# Holiday_r2.net
KiCad netlist of a schematic drawn in Altium Designer
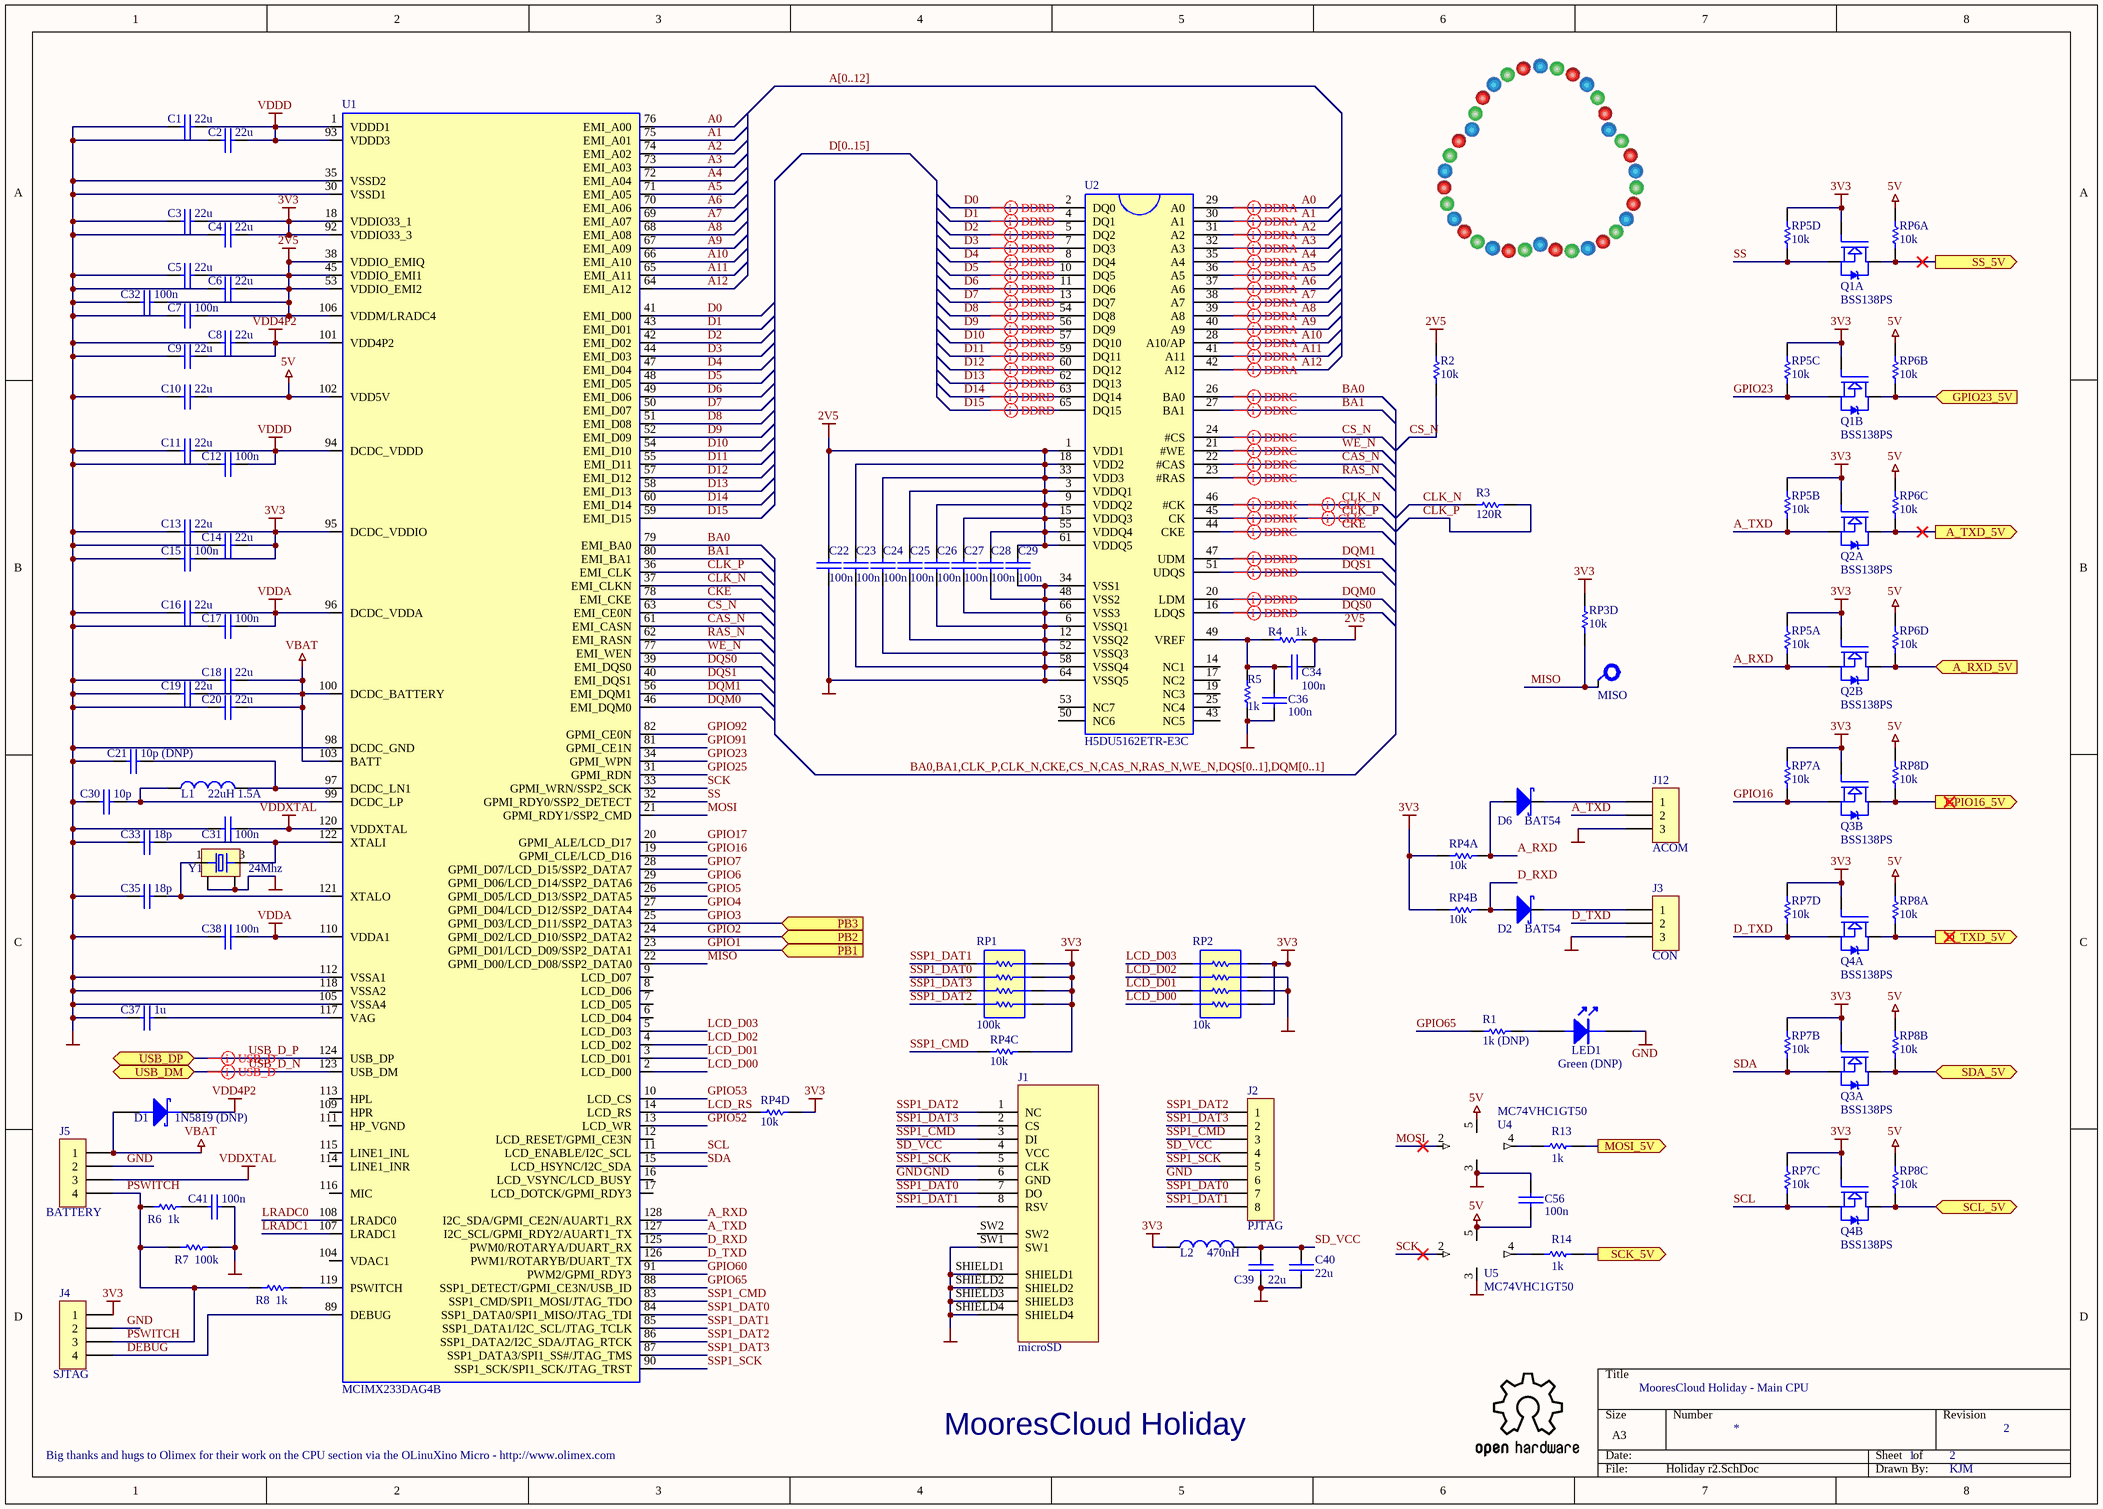
[diagram p0: Holiday r2.SchDoc]

(export (version "E")
  (design (tool "Eeschema 10.0.6"))
  (components
    (comp (ref "C1")
      (value "22u")
      (footprint "ARA_0603")
      (description "Capacitor")
      (libsource (lib "Kean2013") (part "CAP"))
    )
    (comp (ref "C2")
      (value "22u")
      (footprint "ARA_0603")
      (description "Capacitor")
      (libsource (lib "Kean2013") (part "CAP"))
    )
    (comp (ref "C3")
      (value "22u")
      (footprint "ARA_0603")
      (description "Capacitor")
      (libsource (lib "Kean2013") (part "CAP"))
    )
    (comp (ref "C4")
      (value "22u")
      (footprint "ARA_0603")
      (description "Capacitor")
      (libsource (lib "Kean2013") (part "CAP"))
    )
    (comp (ref "C5")
      (value "22u")
      (footprint "ARA_0603")
      (description "Capacitor")
      (libsource (lib "Kean2013") (part "CAP"))
    )
    (comp (ref "C6")
      (value "22u")
      (footprint "ARA_0603")
      (description "Capacitor")
      (libsource (lib "Kean2013") (part "CAP"))
    )
    (comp (ref "C7")
      (value "100n")
      (footprint "ARA_0603")
      (description "Capacitor")
      (libsource (lib "Kean2013") (part "CAP"))
    )
    (comp (ref "C8")
      (value "22u")
      (footprint "ARA_0603")
      (description "Capacitor")
      (libsource (lib "Kean2013") (part "CAP"))
    )
    (comp (ref "C9")
      (value "22u")
      (footprint "ARA_0603")
      (description "Capacitor")
      (libsource (lib "Kean2013") (part "CAP"))
    )
    (comp (ref "C10")
      (value "22u")
      (footprint "ARA_0603")
      (description "Capacitor")
      (libsource (lib "Kean2013") (part "CAP"))
    )
    (comp (ref "C11")
      (value "22u")
      (footprint "ARA_0603")
      (description "Capacitor")
      (libsource (lib "Kean2013") (part "CAP"))
    )
    (comp (ref "C12")
      (value "100n")
      (footprint "ARA_0603")
      (description "Capacitor")
      (libsource (lib "Kean2013") (part "CAP"))
    )
    (comp (ref "C13")
      (value "22u")
      (footprint "ARA_0603")
      (description "Capacitor")
      (libsource (lib "Kean2013") (part "CAP"))
    )
    (comp (ref "C14")
      (value "22u")
      (footprint "ARA_0603")
      (description "Capacitor")
      (libsource (lib "Kean2013") (part "CAP"))
    )
    (comp (ref "C15")
      (value "100n")
      (footprint "ARA_0603")
      (description "Capacitor")
      (libsource (lib "Kean2013") (part "CAP"))
    )
    (comp (ref "C16")
      (value "22u")
      (footprint "ARA_0603")
      (description "Capacitor")
      (libsource (lib "Kean2013") (part "CAP"))
    )
    (comp (ref "C17")
      (value "100n")
      (footprint "ARA_0603")
      (description "Capacitor")
      (libsource (lib "Kean2013") (part "CAP"))
    )
    (comp (ref "C18")
      (value "22u")
      (footprint "ARA_0603")
      (description "Capacitor")
      (libsource (lib "Kean2013") (part "CAP"))
    )
    (comp (ref "C19")
      (value "22u")
      (footprint "ARA_0603")
      (description "Capacitor")
      (libsource (lib "Kean2013") (part "CAP"))
    )
    (comp (ref "C20")
      (value "22u")
      (footprint "ARA_0603")
      (description "Capacitor")
      (libsource (lib "Kean2013") (part "CAP"))
    )
    (comp (ref "C21")
      (value "10p (DNP)")
      (footprint "ARA_0603")
      (description "Capacitor")
      (libsource (lib "Kean2013") (part "CAP"))
    )
    (comp (ref "C22")
      (value "100n")
      (footprint "ARA_0603")
      (description "Capacitor")
      (libsource (lib "Kean2013") (part "CAP"))
    )
    (comp (ref "C23")
      (value "100n")
      (footprint "ARA_0603")
      (description "Capacitor")
      (libsource (lib "Kean2013") (part "CAP"))
    )
    (comp (ref "C24")
      (value "100n")
      (footprint "ARA_0603")
      (description "Capacitor")
      (libsource (lib "Kean2013") (part "CAP"))
    )
    (comp (ref "C25")
      (value "100n")
      (footprint "ARA_0603")
      (description "Capacitor")
      (libsource (lib "Kean2013") (part "CAP"))
    )
    (comp (ref "C26")
      (value "100n")
      (footprint "ARA_0603")
      (description "Capacitor")
      (libsource (lib "Kean2013") (part "CAP"))
    )
    (comp (ref "C27")
      (value "100n")
      (footprint "ARA_0603")
      (description "Capacitor")
      (libsource (lib "Kean2013") (part "CAP"))
    )
    (comp (ref "C28")
      (value "100n")
      (footprint "ARA_0603")
      (description "Capacitor")
      (libsource (lib "Kean2013") (part "CAP"))
    )
    (comp (ref "C29")
      (value "100n")
      (footprint "ARA_0603")
      (description "Capacitor")
      (libsource (lib "Kean2013") (part "CAP"))
    )
    (comp (ref "C30")
      (value "10p")
      (footprint "ARA_0603")
      (description "Capacitor")
      (libsource (lib "Kean2013") (part "CAP"))
    )
    (comp (ref "C31")
      (value "100n")
      (footprint "ARA_0603")
      (description "Capacitor")
      (libsource (lib "Kean2013") (part "CAP"))
    )
    (comp (ref "C32")
      (value "100n")
      (footprint "ARA_0603")
      (description "Capacitor")
      (libsource (lib "Kean2013") (part "CAP"))
    )
    (comp (ref "C33")
      (value "18p")
      (footprint "ARA_0603")
      (description "Capacitor")
      (libsource (lib "Kean2013") (part "CAP"))
    )
    (comp (ref "C34")
      (value "100n")
      (footprint "ARA_0603")
      (description "Capacitor")
      (libsource (lib "Kean2013") (part "CAP"))
    )
    (comp (ref "C35")
      (value "18p")
      (footprint "ARA_0603")
      (description "Capacitor")
      (libsource (lib "Kean2013") (part "CAP"))
    )
    (comp (ref "C36")
      (value "100n")
      (footprint "ARA_0603")
      (description "Capacitor")
      (libsource (lib "Kean2013") (part "CAP"))
    )
    (comp (ref "C37")
      (value "1u")
      (footprint "ARA_0603")
      (description "Capacitor")
      (libsource (lib "Kean2013") (part "CAP"))
    )
    (comp (ref "C38")
      (value "100n")
      (footprint "ARA_0603")
      (description "Capacitor")
      (libsource (lib "Kean2013") (part "CAP"))
    )
    (comp (ref "C39")
      (value "22u")
      (footprint "ARA_0603")
      (description "Capacitor")
      (libsource (lib "Kean2013") (part "CAP"))
    )
    (comp (ref "C40")
      (value "22u")
      (footprint "ARA_0603")
      (description "Capacitor")
      (libsource (lib "Kean2013") (part "CAP"))
    )
    (comp (ref "C41")
      (value "100n")
      (footprint "ARA_0603")
      (description "Capacitor")
      (libsource (lib "Kean2013") (part "CAP"))
    )
    (comp (ref "C56")
      (value "100n")
      (footprint "ARA_0603")
      (description "Capacitor")
      (libsource (lib "Kean2013") (part "CAP"))
    )
    (comp (ref "D1")
      (value "1N5819 (DNP)")
      (footprint "SOD-123")
      (description "Schottky Diode 1N5819HW (DNP)")
      (libsource (lib "Kean2013") (part "DIODE SCHOTTKY"))
    )
    (comp (ref "D2")
      (value "BAT54")
      (footprint "ARA_SOT-23")
      (description "Schottky Diode")
      (libsource (lib "Kean2013") (part "BAT54"))
    )
    (comp (ref "D6")
      (value "BAT54")
      (footprint "ARA_SOT-23")
      (description "Schottky Diode")
      (libsource (lib "Kean2013") (part "BAT54"))
    )
    (comp (ref "J1")
      (value "microSD")
      (footprint "MICROSD-47309-3751 WITH CARD")
      (description "microSD Socket Push/Pull")
      (libsource (lib "Kean2013") (part "microSD"))
    )
    (comp (ref "J2")
      (value "PJTAG")
      (footprint "53047-08")
      (description "Connector")
      (libsource (lib "Kean2013") (part "CON8"))
    )
    (comp (ref "J3")
      (value "CON")
      (footprint "HDR1X3")
      (description "Connector")
      (libsource (lib "Kean2013") (part "CON3"))
    )
    (comp (ref "J4")
      (value "SJTAG")
      (footprint "HDR1X4")
      (description "Connector")
      (libsource (lib "Kean2013") (part "CON4"))
    )
    (comp (ref "J5")
      (value "BATTERY")
      (footprint "HDR1X4")
      (description "Connector")
      (libsource (lib "Kean2013") (part "CON4"))
    )
    (comp (ref "J12")
      (value "ACOM")
      (footprint "HDR1X3")
      (description "Connector")
      (libsource (lib "Kean2013") (part "CON3"))
    )
    (comp (ref "L1")
      (value "22uH 1.5A")
      (footprint "RCL_L7078")
      (description "Inductor")
      (libsource (lib "Kean2013") (part "Inductor"))
    )
    (comp (ref "L2")
      (value "470nH")
      (footprint "ARA_0805")
      (description "Ferrite")
      (libsource (lib "Kean2013") (part "Inductor"))
    )
    (comp (ref "LED1")
      (value "Green (DNP)")
      (footprint "LED_0805")
      (description "LED")
      (libsource (lib "Kean2013") (part "LED"))
    )
    (comp (ref "Q1")
      (value "BSS138PS")
      (footprint "ARA_SOT-363")
      (description "Dual N Channel MOSFET")
      (libsource (lib "Kean2013") (part "BSS138PS"))
    )
    (comp (ref "Q2")
      (value "BSS138PS")
      (footprint "ARA_SOT-363")
      (description "Dual N Channel MOSFET")
      (libsource (lib "Kean2013") (part "BSS138PS"))
    )
    (comp (ref "Q3")
      (value "BSS138PS")
      (footprint "ARA_SOT-363")
      (description "Dual N Channel MOSFET")
      (libsource (lib "Kean2013") (part "BSS138PS"))
    )
    (comp (ref "Q4")
      (value "BSS138PS")
      (footprint "ARA_SOT-363")
      (description "Dual N Channel MOSFET")
      (libsource (lib "Kean2013") (part "BSS138PS"))
    )
    (comp (ref "R1")
      (value "1k (DNP)")
      (footprint "ARA_0603")
      (description "Resistor")
      (libsource (lib "Kean2013") (part "Res Semi"))
    )
    (comp (ref "R2")
      (value "10k")
      (footprint "ARA_0603")
      (description "Resistor")
      (libsource (lib "Kean2013") (part "Res Semi"))
    )
    (comp (ref "R3")
      (value "120R")
      (footprint "ARA_0603")
      (description "Resistor")
      (libsource (lib "Kean2013") (part "Res Semi"))
    )
    (comp (ref "R4")
      (value "1k")
      (footprint "ARA_0603")
      (description "Resistor")
      (libsource (lib "Kean2013") (part "Res Semi"))
    )
    (comp (ref "R5")
      (value "1k")
      (footprint "ARA_0603")
      (description "Resistor")
      (libsource (lib "Kean2013") (part "Res Semi"))
    )
    (comp (ref "R6")
      (value "1k")
      (footprint "ARA_0603")
      (description "Resistor")
      (libsource (lib "Kean2013") (part "Res Semi"))
    )
    (comp (ref "R7")
      (value "100k")
      (footprint "ARA_0603")
      (description "Resistor")
      (libsource (lib "Kean2013") (part "Res Semi"))
    )
    (comp (ref "R8")
      (value "1k")
      (footprint "ARA_0603")
      (description "Resistor")
      (libsource (lib "Kean2013") (part "Res Semi"))
    )
    (comp (ref "R13")
      (value "1k")
      (footprint "ARA_0603")
      (description "Resistor")
      (libsource (lib "Kean2013") (part "Res Semi"))
    )
    (comp (ref "R14")
      (value "1k")
      (footprint "ARA_0603")
      (description "Resistor")
      (libsource (lib "Kean2013") (part "Res Semi"))
    )
    (comp (ref "RP1")
      (value "100k")
      (footprint "RESPACK_0603x4")
      (description "Resistor Pack 4x0603")
      (libsource (lib "Kean2013") (part "RESISTOR_PACK_4_1206"))
    )
    (comp (ref "RP2")
      (value "10k")
      (footprint "RESPACK_0603x4")
      (description "Resistor Pack 4x0603")
      (libsource (lib "Kean2013") (part "RESISTOR_PACK_4_1206"))
    )
    (comp (ref "RP3")
      (value "10k")
      (footprint "RESPACK_0603x4")
      (description "Resistor Pack 4x0603")
      (libsource (lib "Kean2013") (part "RESISTOR_PACK_4_1206_SPLIT"))
    )
    (comp (ref "RP4")
      (value "10k")
      (footprint "RESPACK_0603x4")
      (description "Resistor Pack 4x0603")
      (libsource (lib "Kean2013") (part "RESISTOR_PACK_4_1206_SPLIT"))
    )
    (comp (ref "RP5")
      (value "10k")
      (footprint "RESPACK_0603x4")
      (description "Resistor Pack 4x0603")
      (libsource (lib "Kean2013") (part "RESISTOR_PACK_4_1206_SPLIT"))
    )
    (comp (ref "RP6")
      (value "10k")
      (footprint "RESPACK_0603x4")
      (description "Resistor Pack 4x0603")
      (libsource (lib "Kean2013") (part "RESISTOR_PACK_4_1206_SPLIT"))
    )
    (comp (ref "RP7")
      (value "10k")
      (footprint "RESPACK_0603x4")
      (description "Resistor Pack 4x0603")
      (libsource (lib "Kean2013") (part "RESISTOR_PACK_4_1206_SPLIT"))
    )
    (comp (ref "RP8")
      (value "10k")
      (footprint "RESPACK_0603x4")
      (description "Resistor Pack 4x0603")
      (libsource (lib "Kean2013") (part "RESISTOR_PACK_4_1206_SPLIT"))
    )
    (comp (ref "TP1")
      (value "MISO")
      (footprint "SMD_TESTTERMINAL")
      (description "Test Point")
      (libsource (lib "Kean2013") (part "TESTTERMINAL"))
    )
    (comp (ref "U1")
      (value "MCIMX233DAG4B")
      (footprint "LQFP128")
      (description "Freescale i.MX233 128 pin LQFP package")
      (libsource (lib "Kean2013") (part "MCIMX233DAG4B"))
    )
    (comp (ref "U2")
      (value "H5DU5162ETR-E3C")
      (footprint "TSOP-II-66")
      (description "SDRAM DDR400 66TSOP-II")
      (libsource (lib "Kean2013") (part "H5DU5162ETR-E3C"))
    )
    (comp (ref "U4")
      (value "MC74VHC1GT50")
      (footprint "ARA_SOT-23-5L")
      (description "CMOS Logic Level Shifter")
      (libsource (lib "Kean2013") (part "MC74VHC1GT50"))
    )
    (comp (ref "U5")
      (value "MC74VHC1GT50")
      (footprint "ARA_SOT-23-5L")
      (description "CMOS Logic Level Shifter")
      (libsource (lib "Kean2013") (part "MC74VHC1GT50"))
    )
    (comp (ref "Y1")
      (value "24Mhz")
      (footprint "CRYSTAL_ABMM2")
      (description "ABMM2 SMD Crystal")
      (libsource (lib "Kean2013") (part "CRYSTAL_ABMM2"))
    )
  )
  (nets
    (net (code "2") (name "/A0") (class "Default")
      (node (ref "U1") (pin "76") (pinfunction "EMI_A00_76") (pintype "passive"))
      (node (ref "U2") (pin "29") (pinfunction "A0_29") (pintype "passive"))
    )
    (net (code "3") (name "/A1") (class "Default")
      (node (ref "U1") (pin "75") (pinfunction "EMI_A01_75") (pintype "passive"))
      (node (ref "U2") (pin "30") (pinfunction "A1_30") (pintype "passive"))
    )
    (net (code "4") (name "/A2") (class "Default")
      (node (ref "U1") (pin "74") (pinfunction "EMI_A02_74") (pintype "passive"))
      (node (ref "U2") (pin "31") (pinfunction "A2_31") (pintype "passive"))
    )
    (net (code "5") (name "/A3") (class "Default")
      (node (ref "U1") (pin "73") (pinfunction "EMI_A03_73") (pintype "passive"))
      (node (ref "U2") (pin "32") (pinfunction "A3_32") (pintype "passive"))
    )
    (net (code "6") (name "/A4") (class "Default")
      (node (ref "U1") (pin "72") (pinfunction "EMI_A04_72") (pintype "passive"))
      (node (ref "U2") (pin "35") (pinfunction "A4_35") (pintype "passive"))
    )
    (net (code "7") (name "/A5") (class "Default")
      (node (ref "U1") (pin "71") (pinfunction "EMI_A05_71") (pintype "passive"))
      (node (ref "U2") (pin "36") (pinfunction "A5_36") (pintype "passive"))
    )
    (net (code "8") (name "/A6") (class "Default")
      (node (ref "U1") (pin "70") (pinfunction "EMI_A06_70") (pintype "passive"))
      (node (ref "U2") (pin "37") (pinfunction "A6_37") (pintype "passive"))
    )
    (net (code "9") (name "/A7") (class "Default")
      (node (ref "U1") (pin "69") (pinfunction "EMI_A07_69") (pintype "passive"))
      (node (ref "U2") (pin "38") (pinfunction "A7_38") (pintype "passive"))
    )
    (net (code "10") (name "/A8") (class "Default")
      (node (ref "U1") (pin "68") (pinfunction "EMI_A08_68") (pintype "passive"))
      (node (ref "U2") (pin "39") (pinfunction "A8_39") (pintype "passive"))
    )
    (net (code "11") (name "/A9") (class "Default")
      (node (ref "U1") (pin "67") (pinfunction "EMI_A09_67") (pintype "passive"))
      (node (ref "U2") (pin "40") (pinfunction "A9_40") (pintype "passive"))
    )
    (net (code "12") (name "/A10") (class "Default")
      (node (ref "U1") (pin "66") (pinfunction "EMI_A10_66") (pintype "passive"))
      (node (ref "U2") (pin "28") (pinfunction "A10/AP_28") (pintype "passive"))
    )
    (net (code "13") (name "/A11") (class "Default")
      (node (ref "U1") (pin "65") (pinfunction "EMI_A11_65") (pintype "passive"))
      (node (ref "U2") (pin "41") (pinfunction "A11_41") (pintype "passive"))
    )
    (net (code "14") (name "/A12") (class "Default")
      (node (ref "U1") (pin "64") (pinfunction "EMI_A12_64") (pintype "passive"))
      (node (ref "U2") (pin "42") (pinfunction "A12_42") (pintype "passive"))
    )
    (net (code "16") (name "/A_RXD") (class "Default")
      (node (ref "D6") (pin "1") (pinfunction "A_1") (pintype "passive"))
      (node (ref "Q2") (pin "4") (pinfunction "S2_4") (pintype "passive"))
      (node (ref "RP4") (pin "1.1") (pinfunction "1.1_1.1") (pintype "passive"))
      (node (ref "RP5") (pin "1.1") (pinfunction "1.1_1.1") (pintype "passive"))
      (node (ref "U1") (pin "128") (pinfunction "I2C_SDA/GPMI_CE2N/AUART1_RX_128") (pintype "passive"))
    )
    (net (code "17") (name "/A_RXD_5V") (class "Default")
      (node (ref "Q2") (pin "3") (pinfunction "D2_3") (pintype "passive"))
      (node (ref "RP6") (pin "4.1") (pinfunction "4.1_4.1") (pintype "passive"))
    )
    (net (code "18") (name "/A_TXD") (class "Default")
      (node (ref "J12") (pin "2") (pinfunction "2_2") (pintype "passive"))
      (node (ref "Q2") (pin "1") (pinfunction "S1_1") (pintype "passive"))
      (node (ref "RP5") (pin "2.1") (pinfunction "2.1_2.1") (pintype "passive"))
      (node (ref "U1") (pin "127") (pinfunction "I2C_SCL/GPMI_RDY2/AUART1_TX_127") (pintype "passive"))
    )
    (net (code "19") (name "/A_TXD_5V") (class "Default")
      (node (ref "Q2") (pin "6") (pinfunction "D1_6") (pintype "passive"))
      (node (ref "RP6") (pin "3.1") (pinfunction "3.1_3.1") (pintype "passive"))
    )
    (net (code "20") (name "/BA0") (class "Default")
      (node (ref "U1") (pin "79") (pinfunction "EMI_BA0_79") (pintype "passive"))
      (node (ref "U2") (pin "26") (pinfunction "BA0_26") (pintype "passive"))
    )
    (net (code "21") (name "/BA1") (class "Default")
      (node (ref "U1") (pin "80") (pinfunction "EMI_BA1_80") (pintype "passive"))
      (node (ref "U2") (pin "27") (pinfunction "BA1_27") (pintype "passive"))
    )
    (net (code "22") (name "/CAS_N") (class "Default")
      (node (ref "U1") (pin "61") (pinfunction "EMI_CASN_61") (pintype "passive"))
      (node (ref "U2") (pin "22") (pinfunction "#CAS_22") (pintype "passive"))
    )
    (net (code "23") (name "/CKE") (class "Default")
      (node (ref "U1") (pin "78") (pinfunction "EMI_CKE_78") (pintype "passive"))
      (node (ref "U2") (pin "44") (pinfunction "CKE_44") (pintype "passive"))
    )
    (net (code "24") (name "/CLK_N") (class "Default")
      (node (ref "R3") (pin "1") (pinfunction "1_1") (pintype "passive"))
      (node (ref "U1") (pin "37") (pinfunction "EMI_CLKN_37") (pintype "passive"))
      (node (ref "U2") (pin "46") (pinfunction "#CK_46") (pintype "passive"))
    )
    (net (code "25") (name "/CLK_P") (class "Default")
      (node (ref "R3") (pin "2") (pinfunction "2_2") (pintype "passive"))
      (node (ref "U1") (pin "36") (pinfunction "EMI_CLK_36") (pintype "passive"))
      (node (ref "U2") (pin "45") (pinfunction "CK_45") (pintype "passive"))
    )
    (net (code "26") (name "/CS_N") (class "Default")
      (node (ref "R2") (pin "1") (pinfunction "1_1") (pintype "passive"))
      (node (ref "U1") (pin "63") (pinfunction "EMI_CE0N_63") (pintype "passive"))
      (node (ref "U2") (pin "24") (pinfunction "#CS_24") (pintype "passive"))
    )
    (net (code "27") (name "/D0") (class "Default")
      (node (ref "U1") (pin "41") (pinfunction "EMI_D00_41") (pintype "passive"))
      (node (ref "U2") (pin "2") (pinfunction "DQ0_2") (pintype "passive"))
    )
    (net (code "28") (name "/D1") (class "Default")
      (node (ref "U1") (pin "43") (pinfunction "EMI_D01_43") (pintype "passive"))
      (node (ref "U2") (pin "4") (pinfunction "DQ1_4") (pintype "passive"))
    )
    (net (code "29") (name "/D2") (class "Default")
      (node (ref "U1") (pin "42") (pinfunction "EMI_D02_42") (pintype "passive"))
      (node (ref "U2") (pin "5") (pinfunction "DQ2_5") (pintype "passive"))
    )
    (net (code "30") (name "/D3") (class "Default")
      (node (ref "U1") (pin "44") (pinfunction "EMI_D03_44") (pintype "passive"))
      (node (ref "U2") (pin "7") (pinfunction "DQ3_7") (pintype "passive"))
    )
    (net (code "31") (name "/D4") (class "Default")
      (node (ref "U1") (pin "47") (pinfunction "EMI_D04_47") (pintype "passive"))
      (node (ref "U2") (pin "8") (pinfunction "DQ4_8") (pintype "passive"))
    )
    (net (code "32") (name "/D5") (class "Default")
      (node (ref "U1") (pin "48") (pinfunction "EMI_D05_48") (pintype "passive"))
      (node (ref "U2") (pin "10") (pinfunction "DQ5_10") (pintype "passive"))
    )
    (net (code "33") (name "/D6") (class "Default")
      (node (ref "U1") (pin "49") (pinfunction "EMI_D06_49") (pintype "passive"))
      (node (ref "U2") (pin "11") (pinfunction "DQ6_11") (pintype "passive"))
    )
    (net (code "34") (name "/D7") (class "Default")
      (node (ref "U1") (pin "50") (pinfunction "EMI_D07_50") (pintype "passive"))
      (node (ref "U2") (pin "13") (pinfunction "DQ7_13") (pintype "passive"))
    )
    (net (code "35") (name "/D8") (class "Default")
      (node (ref "U1") (pin "51") (pinfunction "EMI_D08_51") (pintype "passive"))
      (node (ref "U2") (pin "54") (pinfunction "DQ8_54") (pintype "passive"))
    )
    (net (code "36") (name "/D9") (class "Default")
      (node (ref "U1") (pin "52") (pinfunction "EMI_D09_52") (pintype "passive"))
      (node (ref "U2") (pin "56") (pinfunction "DQ9_56") (pintype "passive"))
    )
    (net (code "37") (name "/D10") (class "Default")
      (node (ref "U1") (pin "54") (pinfunction "EMI_D10_54") (pintype "passive"))
      (node (ref "U2") (pin "57") (pinfunction "DQ10_57") (pintype "passive"))
    )
    (net (code "38") (name "/D11") (class "Default")
      (node (ref "U1") (pin "55") (pinfunction "EMI_D11_55") (pintype "passive"))
      (node (ref "U2") (pin "59") (pinfunction "DQ11_59") (pintype "passive"))
    )
    (net (code "39") (name "/D12") (class "Default")
      (node (ref "U1") (pin "57") (pinfunction "EMI_D12_57") (pintype "passive"))
      (node (ref "U2") (pin "60") (pinfunction "DQ12_60") (pintype "passive"))
    )
    (net (code "40") (name "/D13") (class "Default")
      (node (ref "U1") (pin "58") (pinfunction "EMI_D13_58") (pintype "passive"))
      (node (ref "U2") (pin "62") (pinfunction "DQ13_62") (pintype "passive"))
    )
    (net (code "41") (name "/D14") (class "Default")
      (node (ref "U1") (pin "60") (pinfunction "EMI_D14_60") (pintype "passive"))
      (node (ref "U2") (pin "63") (pinfunction "DQ14_63") (pintype "passive"))
    )
    (net (code "42") (name "/D15") (class "Default")
      (node (ref "U1") (pin "59") (pinfunction "EMI_D15_59") (pintype "passive"))
      (node (ref "U2") (pin "65") (pinfunction "DQ15_65") (pintype "passive"))
    )
    (net (code "43") (name "/DEBUG") (class "Default")
      (node (ref "J4") (pin "4") (pinfunction "4_4") (pintype "passive"))
      (node (ref "U1") (pin "89") (pinfunction "DEBUG_89") (pintype "passive"))
    )
    (net (code "44") (name "/DQM0") (class "Default")
      (node (ref "U1") (pin "46") (pinfunction "EMI_DQM0_46") (pintype "passive"))
      (node (ref "U2") (pin "20") (pinfunction "LDM_20") (pintype "passive"))
    )
    (net (code "45") (name "/DQM1") (class "Default")
      (node (ref "U1") (pin "56") (pinfunction "EMI_DQM1_56") (pintype "passive"))
      (node (ref "U2") (pin "47") (pinfunction "UDM_47") (pintype "passive"))
    )
    (net (code "46") (name "/DQS0") (class "Default")
      (node (ref "U1") (pin "39") (pinfunction "EMI_DQS0_39") (pintype "passive"))
      (node (ref "U2") (pin "16") (pinfunction "LDQS_16") (pintype "passive"))
    )
    (net (code "47") (name "/DQS1") (class "Default")
      (node (ref "U1") (pin "40") (pinfunction "EMI_DQS1_40") (pintype "passive"))
      (node (ref "U2") (pin "51") (pinfunction "UDQS_51") (pintype "passive"))
    )
    (net (code "49") (name "/D_RXD") (class "Default")
      (node (ref "D2") (pin "1") (pinfunction "A_1") (pintype "passive"))
      (node (ref "RP4") (pin "2.1") (pinfunction "2.1_2.1") (pintype "passive"))
      (node (ref "U1") (pin "125") (pinfunction "PWM0/ROTARYA/DUART_RX_125") (pintype "passive"))
    )
    (net (code "50") (name "/D_TXD") (class "Default")
      (node (ref "J3") (pin "2") (pinfunction "2_2") (pintype "passive"))
      (node (ref "Q4") (pin "1") (pinfunction "S1_1") (pintype "passive"))
      (node (ref "RP7") (pin "4.1") (pinfunction "4.1_4.1") (pintype "passive"))
      (node (ref "U1") (pin "126") (pinfunction "PWM1/ROTARYB/DUART_TX_126") (pintype "passive"))
    )
    (net (code "51") (name "/D_TXD_5V") (class "Default")
      (node (ref "Q4") (pin "6") (pinfunction "D1_6") (pintype "passive"))
      (node (ref "RP8") (pin "1.1") (pinfunction "1.1_1.1") (pintype "passive"))
    )
    (net (code "52") (name "/GPIO1") (class "Default")
      (node (ref "U1") (pin "23") (pinfunction "GPMI_D01/LCD_D09/SSP2_DATA1_23") (pintype "passive"))
    )
    (net (code "53") (name "/GPIO2") (class "Default")
      (node (ref "U1") (pin "24") (pinfunction "GPMI_D02/LCD_D10/SSP2_DATA2_24") (pintype "passive"))
    )
    (net (code "54") (name "/GPIO3") (class "Default")
      (node (ref "U1") (pin "25") (pinfunction "GPMI_D03/LCD_D11/SSP2_DATA3_25") (pintype "passive"))
    )
    (net (code "55") (name "/GPIO4") (class "Default")
      (node (ref "U1") (pin "27") (pinfunction "GPMI_D04/LCD_D12/SSP2_DATA4_27") (pintype "passive"))
    )
    (net (code "56") (name "/GPIO5") (class "Default")
      (node (ref "U1") (pin "26") (pinfunction "GPMI_D05/LCD_D13/SSP2_DATA5_26") (pintype "passive"))
    )
    (net (code "57") (name "/GPIO6") (class "Default")
      (node (ref "U1") (pin "29") (pinfunction "GPMI_D06/LCD_D14/SSP2_DATA6_29") (pintype "passive"))
    )
    (net (code "58") (name "/GPIO7") (class "Default")
      (node (ref "U1") (pin "28") (pinfunction "GPMI_D07/LCD_D15/SSP2_DATA7_28") (pintype "passive"))
    )
    (net (code "59") (name "/GPIO16") (class "Default")
      (node (ref "Q3") (pin "4") (pinfunction "S2_4") (pintype "passive"))
      (node (ref "RP7") (pin "1.1") (pinfunction "1.1_1.1") (pintype "passive"))
      (node (ref "U1") (pin "19") (pinfunction "GPMI_CLE/LCD_D16_19") (pintype "passive"))
    )
    (net (code "60") (name "/GPIO16_5V") (class "Default")
      (node (ref "Q3") (pin "3") (pinfunction "D2_3") (pintype "passive"))
      (node (ref "RP8") (pin "4.1") (pinfunction "4.1_4.1") (pintype "passive"))
    )
    (net (code "61") (name "/GPIO17") (class "Default")
      (node (ref "U1") (pin "20") (pinfunction "GPMI_ALE/LCD_D17_20") (pintype "passive"))
    )
    (net (code "62") (name "/GPIO23") (class "Default")
      (node (ref "Q1") (pin "4") (pinfunction "S2_4") (pintype "passive"))
      (node (ref "RP5") (pin "3.1") (pinfunction "3.1_3.1") (pintype "passive"))
      (node (ref "U1") (pin "34") (pinfunction "GPMI_WPN_34") (pintype "passive"))
    )
    (net (code "63") (name "/GPIO23_5V") (class "Default")
      (node (ref "Q1") (pin "3") (pinfunction "D2_3") (pintype "passive"))
      (node (ref "RP6") (pin "2.1") (pinfunction "2.1_2.1") (pintype "passive"))
    )
    (net (code "64") (name "/GPIO25") (class "Default")
      (node (ref "U1") (pin "31") (pinfunction "GPMI_RDN_31") (pintype "passive"))
    )
    (net (code "65") (name "/GPIO52") (class "Default")
      (node (ref "U1") (pin "13") (pinfunction "LCD_WR_13") (pintype "passive"))
    )
    (net (code "66") (name "/GPIO53") (class "Default")
      (node (ref "U1") (pin "10") (pinfunction "LCD_CS_10") (pintype "passive"))
    )
    (net (code "67") (name "/GPIO60") (class "Default")
      (node (ref "U1") (pin "91") (pinfunction "PWM2/GPMI_RDY3_91") (pintype "passive"))
    )
    (net (code "68") (name "/GPIO65") (class "Default")
      (node (ref "R1") (pin "2") (pinfunction "2_2") (pintype "passive"))
      (node (ref "U1") (pin "88") (pinfunction "SSP1_DETECT/GPMI_CE3N/USB_ID_88") (pintype "passive"))
    )
    (net (code "69") (name "/GPIO91") (class "Default")
      (node (ref "U1") (pin "81") (pinfunction "GPMI_CE1N_81") (pintype "passive"))
    )
    (net (code "70") (name "/GPIO92") (class "Default")
      (node (ref "U1") (pin "82") (pinfunction "GPMI_CE0N_82") (pintype "passive"))
    )
    (net (code "71") (name "/LCD_D00") (class "Default")
      (node (ref "RP2") (pin "4.1") (pinfunction "4.1_4.1") (pintype "passive"))
      (node (ref "U1") (pin "2") (pinfunction "LCD_D00_2") (pintype "passive"))
    )
    (net (code "72") (name "/LCD_D01") (class "Default")
      (node (ref "RP2") (pin "3.1") (pinfunction "3.1_3.1") (pintype "passive"))
      (node (ref "U1") (pin "3") (pinfunction "LCD_D01_3") (pintype "passive"))
    )
    (net (code "73") (name "/LCD_D02") (class "Default")
      (node (ref "RP2") (pin "2.1") (pinfunction "2.1_2.1") (pintype "passive"))
      (node (ref "U1") (pin "4") (pinfunction "LCD_D02_4") (pintype "passive"))
    )
    (net (code "74") (name "/LCD_D03") (class "Default")
      (node (ref "RP2") (pin "1.1") (pinfunction "1.1_1.1") (pintype "passive"))
      (node (ref "U1") (pin "5") (pinfunction "LCD_D03_5") (pintype "passive"))
    )
    (net (code "75") (name "/LCD_RS") (class "Default")
      (node (ref "RP4") (pin "4.1") (pinfunction "4.1_4.1") (pintype "passive"))
      (node (ref "U1") (pin "14") (pinfunction "LCD_RS_14") (pintype "passive"))
    )
    (net (code "76") (name "/LRADC0") (class "Default")
      (node (ref "U1") (pin "108") (pinfunction "LRADC0_108") (pintype "passive"))
    )
    (net (code "77") (name "/LRADC1") (class "Default")
      (node (ref "U1") (pin "107") (pinfunction "LRADC1_107") (pintype "passive"))
    )
    (net (code "78") (name "/MISO") (class "Default")
      (node (ref "RP3") (pin "4.1") (pinfunction "4.1_4.1") (pintype "passive"))
      (node (ref "TP1") (pin "1") (pintype "passive"))
      (node (ref "U1") (pin "22") (pinfunction "GPMI_D00/LCD_D08/SSP2_DATA0_22") (pintype "passive"))
    )
    (net (code "79") (name "/MOSI") (class "Default")
      (node (ref "U1") (pin "21") (pinfunction "GPMI_RDY1/SSP2_CMD_21") (pintype "passive"))
      (node (ref "U4") (pin "2") (pinfunction "IN_2") (pintype "input"))
    )
    (net (code "80") (name "/MOSI_5V") (class "Default")
      (node (ref "R13") (pin "1") (pinfunction "1_1") (pintype "passive"))
    )
    (net (code "81") (name "/PSWITCH") (class "Default")
      (node (ref "J4") (pin "3") (pinfunction "3_3") (pintype "passive"))
      (node (ref "J5") (pin "4") (pinfunction "4_4") (pintype "passive"))
      (node (ref "R6") (pin "2") (pinfunction "2_2") (pintype "passive"))
      (node (ref "R7") (pin "2") (pinfunction "2_2") (pintype "passive"))
      (node (ref "R8") (pin "2") (pinfunction "2_2") (pintype "passive"))
    )
    (net (code "82") (name "/RAS_N") (class "Default")
      (node (ref "U1") (pin "62") (pinfunction "EMI_RASN_62") (pintype "passive"))
      (node (ref "U2") (pin "23") (pinfunction "#RAS_23") (pintype "passive"))
    )
    (net (code "83") (name "/SCK") (class "Default")
      (node (ref "U1") (pin "33") (pinfunction "GPMI_WRN/SSP2_SCK_33") (pintype "passive"))
      (node (ref "U5") (pin "2") (pinfunction "IN_2") (pintype "input"))
    )
    (net (code "84") (name "/SCK_5V") (class "Default")
      (node (ref "R14") (pin "1") (pinfunction "1_1") (pintype "passive"))
    )
    (net (code "85") (name "/SCL") (class "Default")
      (node (ref "Q4") (pin "4") (pinfunction "S2_4") (pintype "passive"))
      (node (ref "RP7") (pin "3.1") (pinfunction "3.1_3.1") (pintype "passive"))
      (node (ref "U1") (pin "11") (pinfunction "LCD_ENABLE/I2C_SCL_11") (pintype "passive"))
    )
    (net (code "86") (name "/SCL_5V") (class "Default")
      (node (ref "Q4") (pin "3") (pinfunction "D2_3") (pintype "passive"))
      (node (ref "RP8") (pin "3.1") (pinfunction "3.1_3.1") (pintype "passive"))
    )
    (net (code "87") (name "/SDA") (class "Default")
      (node (ref "Q3") (pin "1") (pinfunction "S1_1") (pintype "passive"))
      (node (ref "RP7") (pin "2.1") (pinfunction "2.1_2.1") (pintype "passive"))
      (node (ref "U1") (pin "15") (pinfunction "LCD_HSYNC/I2C_SDA_15") (pintype "passive"))
    )
    (net (code "88") (name "/SDA_5V") (class "Default")
      (node (ref "Q3") (pin "6") (pinfunction "D1_6") (pintype "passive"))
      (node (ref "RP8") (pin "2.1") (pinfunction "2.1_2.1") (pintype "passive"))
    )
    (net (code "89") (name "/SD_VCC") (class "Default")
      (node (ref "C39") (pin "1") (pinfunction "1_1") (pintype "passive"))
      (node (ref "C40") (pin "1") (pinfunction "1_1") (pintype "passive"))
      (node (ref "J1") (pin "4") (pinfunction "VCC_4") (pintype "passive"))
      (node (ref "J2") (pin "4") (pinfunction "4_4") (pintype "passive"))
      (node (ref "L2") (pin "1") (pinfunction "1_1") (pintype "passive"))
    )
    (net (code "90") (name "/SS") (class "Default")
      (node (ref "Q1") (pin "1") (pinfunction "S1_1") (pintype "passive"))
      (node (ref "RP5") (pin "4.1") (pinfunction "4.1_4.1") (pintype "passive"))
      (node (ref "U1") (pin "32") (pinfunction "GPMI_RDY0/SSP2_DETECT_32") (pintype "passive"))
    )
    (net (code "91") (name "/SSP1_CMD") (class "Default")
      (node (ref "J1") (pin "3") (pinfunction "DI_3") (pintype "passive"))
      (node (ref "J2") (pin "3") (pinfunction "3_3") (pintype "passive"))
      (node (ref "RP4") (pin "3.1") (pinfunction "3.1_3.1") (pintype "passive"))
      (node (ref "U1") (pin "83") (pinfunction "SSP1_CMD/SPI1_MOSI/JTAG_TDO_83") (pintype "passive"))
    )
    (net (code "92") (name "/SSP1_DAT0") (class "Default")
      (node (ref "J1") (pin "7") (pinfunction "DO_7") (pintype "passive"))
      (node (ref "J2") (pin "7") (pinfunction "7_7") (pintype "passive"))
      (node (ref "RP1") (pin "2.1") (pinfunction "2.1_2.1") (pintype "passive"))
      (node (ref "U1") (pin "84") (pinfunction "SSP1_DATA0/SPI1_MISO/JTAG_TDI_84") (pintype "passive"))
    )
    (net (code "93") (name "/SSP1_DAT1") (class "Default")
      (node (ref "J1") (pin "8") (pinfunction "RSV_8") (pintype "passive"))
      (node (ref "J2") (pin "8") (pinfunction "8_8") (pintype "passive"))
      (node (ref "RP1") (pin "1.1") (pinfunction "1.1_1.1") (pintype "passive"))
      (node (ref "U1") (pin "85") (pinfunction "SSP1_DATA1/I2C_SCL/JTAG_TCLK_85") (pintype "passive"))
    )
    (net (code "94") (name "/SSP1_DAT2") (class "Default")
      (node (ref "J1") (pin "1") (pinfunction "NC_1") (pintype "passive"))
      (node (ref "J2") (pin "1") (pinfunction "1_1") (pintype "passive"))
      (node (ref "RP1") (pin "4.1") (pinfunction "4.1_4.1") (pintype "passive"))
      (node (ref "U1") (pin "86") (pinfunction "SSP1_DATA2/I2C_SDA/JTAG_RTCK_86") (pintype "passive"))
    )
    (net (code "95") (name "/SSP1_DAT3") (class "Default")
      (node (ref "J1") (pin "2") (pinfunction "CS_2") (pintype "passive"))
      (node (ref "J2") (pin "2") (pinfunction "2_2") (pintype "passive"))
      (node (ref "RP1") (pin "3.1") (pinfunction "3.1_3.1") (pintype "passive"))
      (node (ref "U1") (pin "87") (pinfunction "SSP1_DATA3/SPI1_SS#/JTAG_TMS_87") (pintype "passive"))
    )
    (net (code "96") (name "/SSP1_SCK") (class "Default")
      (node (ref "J1") (pin "5") (pinfunction "CLK_5") (pintype "passive"))
      (node (ref "J2") (pin "5") (pinfunction "5_5") (pintype "passive"))
      (node (ref "U1") (pin "90") (pinfunction "SSP1_SCK/SPI1_SCK/JTAG_TRST_90") (pintype "passive"))
    )
    (net (code "97") (name "/SS_5V") (class "Default")
      (node (ref "Q1") (pin "6") (pinfunction "D1_6") (pintype "passive"))
      (node (ref "RP6") (pin "1.1") (pinfunction "1.1_1.1") (pintype "passive"))
    )
    (net (code "98") (name "/USB_D_N") (class "Default")
      (node (ref "U1") (pin "123") (pinfunction "USB_DM_123") (pintype "passive"))
    )
    (net (code "99") (name "/USB_D_P") (class "Default")
      (node (ref "U1") (pin "124") (pinfunction "USB_DP_124") (pintype "passive"))
    )
    (net (code "100") (name "/WE_N") (class "Default")
      (node (ref "U1") (pin "77") (pinfunction "EMI_WEN_77") (pintype "passive"))
      (node (ref "U2") (pin "21") (pinfunction "#WE_21") (pintype "passive"))
    )
    (net (code "102") (name "2V5") (class "Default")
      (node (ref "C22") (pin "1") (pinfunction "1_1") (pintype "passive"))
      (node (ref "C23") (pin "1") (pinfunction "1_1") (pintype "passive"))
      (node (ref "C24") (pin "1") (pinfunction "1_1") (pintype "passive"))
      (node (ref "C25") (pin "1") (pinfunction "1_1") (pintype "passive"))
      (node (ref "C26") (pin "1") (pinfunction "1_1") (pintype "passive"))
      (node (ref "C27") (pin "1") (pinfunction "1_1") (pintype "passive"))
      (node (ref "C28") (pin "1") (pinfunction "1_1") (pintype "passive"))
      (node (ref "C29") (pin "1") (pinfunction "1_1") (pintype "passive"))
      (node (ref "C32") (pin "1") (pinfunction "1_1") (pintype "passive"))
      (node (ref "C34") (pin "1") (pinfunction "1_1") (pintype "passive"))
      (node (ref "C5") (pin "1") (pinfunction "1_1") (pintype "passive"))
      (node (ref "C6") (pin "1") (pinfunction "1_1") (pintype "passive"))
      (node (ref "C7") (pin "1") (pinfunction "1_1") (pintype "passive"))
      (node (ref "R2") (pin "2") (pinfunction "2_2") (pintype "passive"))
      (node (ref "R4") (pin "2") (pinfunction "2_2") (pintype "passive"))
      (node (ref "U1") (pin "106") (pinfunction "VDDM/LRADC4_106") (pintype "passive"))
      (node (ref "U1") (pin "38") (pinfunction "VDDIO_EMIQ_38") (pintype "passive"))
      (node (ref "U1") (pin "45") (pinfunction "VDDIO_EMI1_45") (pintype "passive"))
      (node (ref "U1") (pin "53") (pinfunction "VDDIO_EMI2_53") (pintype "passive"))
      (node (ref "U2") (pin "1") (pinfunction "VDD1_1") (pintype "passive"))
      (node (ref "U2") (pin "15") (pinfunction "VDDQ3_15") (pintype "passive"))
      (node (ref "U2") (pin "18") (pinfunction "VDD2_18") (pintype "passive"))
      (node (ref "U2") (pin "3") (pinfunction "VDDQ1_3") (pintype "passive"))
      (node (ref "U2") (pin "33") (pinfunction "VDD3_33") (pintype "passive"))
      (node (ref "U2") (pin "55") (pinfunction "VDDQ4_55") (pintype "passive"))
      (node (ref "U2") (pin "61") (pinfunction "VDDQ5_61") (pintype "passive"))
      (node (ref "U2") (pin "9") (pinfunction "VDDQ2_9") (pintype "passive"))
    )
    (net (code "103") (name "3V3") (class "Default")
      (node (ref "C13") (pin "1") (pinfunction "1_1") (pintype "passive"))
      (node (ref "C14") (pin "1") (pinfunction "1_1") (pintype "passive"))
      (node (ref "C15") (pin "1") (pinfunction "1_1") (pintype "passive"))
      (node (ref "C3") (pin "1") (pinfunction "1_1") (pintype "passive"))
      (node (ref "C4") (pin "1") (pinfunction "1_1") (pintype "passive"))
      (node (ref "J4") (pin "1") (pinfunction "1_1") (pintype "passive"))
      (node (ref "L2") (pin "2") (pinfunction "2_2") (pintype "passive"))
      (node (ref "Q1") (pin "2") (pinfunction "G1_2") (pintype "passive"))
      (node (ref "Q1") (pin "5") (pinfunction "G2_5") (pintype "passive"))
      (node (ref "Q2") (pin "2") (pinfunction "G1_2") (pintype "passive"))
      (node (ref "Q2") (pin "5") (pinfunction "G2_5") (pintype "passive"))
      (node (ref "Q3") (pin "2") (pinfunction "G1_2") (pintype "passive"))
      (node (ref "Q3") (pin "5") (pinfunction "G2_5") (pintype "passive"))
      (node (ref "Q4") (pin "2") (pinfunction "G1_2") (pintype "passive"))
      (node (ref "Q4") (pin "5") (pinfunction "G2_5") (pintype "passive"))
      (node (ref "RP1") (pin "1.2") (pinfunction "1.2_1.2") (pintype "passive"))
      (node (ref "RP1") (pin "2.2") (pinfunction "2.2_2.2") (pintype "passive"))
      (node (ref "RP1") (pin "3.2") (pinfunction "3.2_3.2") (pintype "passive"))
      (node (ref "RP1") (pin "4.2") (pinfunction "4.2_4.2") (pintype "passive"))
      (node (ref "RP2") (pin "1.2") (pinfunction "1.2_1.2") (pintype "passive"))
      (node (ref "RP2") (pin "4.2") (pinfunction "4.2_4.2") (pintype "passive"))
      (node (ref "RP3") (pin "4.2") (pinfunction "4.2_4.2") (pintype "passive"))
      (node (ref "RP4") (pin "1.2") (pinfunction "1.2_1.2") (pintype "passive"))
      (node (ref "RP4") (pin "2.2") (pinfunction "2.2_2.2") (pintype "passive"))
      (node (ref "RP4") (pin "3.2") (pinfunction "3.2_3.2") (pintype "passive"))
      (node (ref "RP4") (pin "4.2") (pinfunction "4.2_4.2") (pintype "passive"))
      (node (ref "RP5") (pin "1.2") (pinfunction "1.2_1.2") (pintype "passive"))
      (node (ref "RP5") (pin "2.2") (pinfunction "2.2_2.2") (pintype "passive"))
      (node (ref "RP5") (pin "3.2") (pinfunction "3.2_3.2") (pintype "passive"))
      (node (ref "RP5") (pin "4.2") (pinfunction "4.2_4.2") (pintype "passive"))
      (node (ref "RP7") (pin "1.2") (pinfunction "1.2_1.2") (pintype "passive"))
      (node (ref "RP7") (pin "2.2") (pinfunction "2.2_2.2") (pintype "passive"))
      (node (ref "RP7") (pin "3.2") (pinfunction "3.2_3.2") (pintype "passive"))
      (node (ref "RP7") (pin "4.2") (pinfunction "4.2_4.2") (pintype "passive"))
      (node (ref "U1") (pin "18") (pinfunction "VDDIO33_1_18") (pintype "passive"))
      (node (ref "U1") (pin "92") (pinfunction "VDDIO33_3_92") (pintype "passive"))
      (node (ref "U1") (pin "95") (pinfunction "DCDC_VDDIO_95") (pintype "passive"))
    )
    (net (code "104") (name "5V") (class "Default")
      (node (ref "C10") (pin "1") (pinfunction "1_1") (pintype "passive"))
      (node (ref "C56") (pin "2") (pinfunction "2_2") (pintype "passive"))
      (node (ref "RP6") (pin "1.2") (pinfunction "1.2_1.2") (pintype "passive"))
      (node (ref "RP6") (pin "2.2") (pinfunction "2.2_2.2") (pintype "passive"))
      (node (ref "RP6") (pin "3.2") (pinfunction "3.2_3.2") (pintype "passive"))
      (node (ref "RP6") (pin "4.2") (pinfunction "4.2_4.2") (pintype "passive"))
      (node (ref "RP8") (pin "1.2") (pinfunction "1.2_1.2") (pintype "passive"))
      (node (ref "RP8") (pin "2.2") (pinfunction "2.2_2.2") (pintype "passive"))
      (node (ref "RP8") (pin "3.2") (pinfunction "3.2_3.2") (pintype "passive"))
      (node (ref "RP8") (pin "4.2") (pinfunction "4.2_4.2") (pintype "passive"))
      (node (ref "U1") (pin "102") (pinfunction "VDD5V_102") (pintype "passive"))
      (node (ref "U4") (pin "5") (pinfunction "VCC_5") (pintype "power_in"))
      (node (ref "U5") (pin "5") (pinfunction "VCC_5") (pintype "power_in"))
    )
    (net (code "105") (name "GND") (class "Default")
      (node (ref "C1") (pin "2") (pinfunction "2_2") (pintype "passive"))
      (node (ref "C10") (pin "2") (pinfunction "2_2") (pintype "passive"))
      (node (ref "C11") (pin "2") (pinfunction "2_2") (pintype "passive"))
      (node (ref "C12") (pin "2") (pinfunction "2_2") (pintype "passive"))
      (node (ref "C13") (pin "2") (pinfunction "2_2") (pintype "passive"))
      (node (ref "C14") (pin "2") (pinfunction "2_2") (pintype "passive"))
      (node (ref "C15") (pin "2") (pinfunction "2_2") (pintype "passive"))
      (node (ref "C16") (pin "2") (pinfunction "2_2") (pintype "passive"))
      (node (ref "C17") (pin "2") (pinfunction "2_2") (pintype "passive"))
      (node (ref "C18") (pin "2") (pinfunction "2_2") (pintype "passive"))
      (node (ref "C19") (pin "2") (pinfunction "2_2") (pintype "passive"))
      (node (ref "C2") (pin "2") (pinfunction "2_2") (pintype "passive"))
      (node (ref "C20") (pin "2") (pinfunction "2_2") (pintype "passive"))
      (node (ref "C21") (pin "2") (pinfunction "2_2") (pintype "passive"))
      (node (ref "C22") (pin "2") (pinfunction "2_2") (pintype "passive"))
      (node (ref "C23") (pin "2") (pinfunction "2_2") (pintype "passive"))
      (node (ref "C24") (pin "2") (pinfunction "2_2") (pintype "passive"))
      (node (ref "C25") (pin "2") (pinfunction "2_2") (pintype "passive"))
      (node (ref "C26") (pin "2") (pinfunction "2_2") (pintype "passive"))
      (node (ref "C27") (pin "2") (pinfunction "2_2") (pintype "passive"))
      (node (ref "C28") (pin "2") (pinfunction "2_2") (pintype "passive"))
      (node (ref "C29") (pin "2") (pinfunction "2_2") (pintype "passive"))
      (node (ref "C3") (pin "2") (pinfunction "2_2") (pintype "passive"))
      (node (ref "C30") (pin "2") (pinfunction "2_2") (pintype "passive"))
      (node (ref "C31") (pin "2") (pinfunction "2_2") (pintype "passive"))
      (node (ref "C32") (pin "2") (pinfunction "2_2") (pintype "passive"))
      (node (ref "C33") (pin "2") (pinfunction "2_2") (pintype "passive"))
      (node (ref "C35") (pin "2") (pinfunction "2_2") (pintype "passive"))
      (node (ref "C36") (pin "2") (pinfunction "2_2") (pintype "passive"))
      (node (ref "C37") (pin "2") (pinfunction "2_2") (pintype "passive"))
      (node (ref "C38") (pin "2") (pinfunction "2_2") (pintype "passive"))
      (node (ref "C39") (pin "2") (pinfunction "2_2") (pintype "passive"))
      (node (ref "C4") (pin "2") (pinfunction "2_2") (pintype "passive"))
      (node (ref "C40") (pin "2") (pinfunction "2_2") (pintype "passive"))
      (node (ref "C41") (pin "2") (pinfunction "2_2") (pintype "passive"))
      (node (ref "C5") (pin "2") (pinfunction "2_2") (pintype "passive"))
      (node (ref "C56") (pin "1") (pinfunction "1_1") (pintype "passive"))
      (node (ref "C6") (pin "2") (pinfunction "2_2") (pintype "passive"))
      (node (ref "C7") (pin "2") (pinfunction "2_2") (pintype "passive"))
      (node (ref "C8") (pin "2") (pinfunction "2_2") (pintype "passive"))
      (node (ref "C9") (pin "2") (pinfunction "2_2") (pintype "passive"))
      (node (ref "J1") (pin "6") (pinfunction "GND_6") (pintype "passive"))
      (node (ref "J1") (pin "SHIELD1") (pinfunction "SHIELD1_SHIELD1") (pintype "passive"))
      (node (ref "J1") (pin "SHIELD2") (pinfunction "SHIELD2_SHIELD2") (pintype "passive"))
      (node (ref "J1") (pin "SHIELD3") (pinfunction "SHIELD3_SHIELD3") (pintype "passive"))
      (node (ref "J1") (pin "SHIELD4") (pinfunction "SHIELD4_SHIELD4") (pintype "passive"))
      (node (ref "J1") (pin "SW1") (pinfunction "SW1_SW1") (pintype "passive"))
      (node (ref "J12") (pin "3") (pinfunction "3_3") (pintype "passive"))
      (node (ref "J2") (pin "6") (pinfunction "6_6") (pintype "passive"))
      (node (ref "J3") (pin "3") (pinfunction "3_3") (pintype "passive"))
      (node (ref "J4") (pin "2") (pinfunction "2_2") (pintype "passive"))
      (node (ref "J5") (pin "2") (pinfunction "2_2") (pintype "passive"))
      (node (ref "LED1") (pin "K") (pinfunction "2_K") (pintype "passive"))
      (node (ref "R5") (pin "2") (pinfunction "2_2") (pintype "passive"))
      (node (ref "R7") (pin "1") (pinfunction "1_1") (pintype "passive"))
      (node (ref "RP2") (pin "2.2") (pinfunction "2.2_2.2") (pintype "passive"))
      (node (ref "RP2") (pin "3.2") (pinfunction "3.2_3.2") (pintype "passive"))
      (node (ref "U1") (pin "105") (pinfunction "VSSA4_105") (pintype "passive"))
      (node (ref "U1") (pin "112") (pinfunction "VSSA1_112") (pintype "passive"))
      (node (ref "U1") (pin "118") (pinfunction "VSSA2_118") (pintype "passive"))
      (node (ref "U1") (pin "30") (pinfunction "VSSD1_30") (pintype "passive"))
      (node (ref "U1") (pin "35") (pinfunction "VSSD2_35") (pintype "passive"))
      (node (ref "U1") (pin "98") (pinfunction "DCDC_GND_98") (pintype "passive"))
      (node (ref "U2") (pin "12") (pinfunction "VSSQ2_12") (pintype "passive"))
      (node (ref "U2") (pin "34") (pinfunction "VSS1_34") (pintype "passive"))
      (node (ref "U2") (pin "48") (pinfunction "VSS2_48") (pintype "passive"))
      (node (ref "U2") (pin "52") (pinfunction "VSSQ3_52") (pintype "passive"))
      (node (ref "U2") (pin "58") (pinfunction "VSSQ4_58") (pintype "passive"))
      (node (ref "U2") (pin "6") (pinfunction "VSSQ1_6") (pintype "passive"))
      (node (ref "U2") (pin "64") (pinfunction "VSSQ5_64") (pintype "passive"))
      (node (ref "U2") (pin "66") (pinfunction "VSS3_66") (pintype "passive"))
      (node (ref "U4") (pin "3") (pinfunction "GND_3") (pintype "power_in"))
      (node (ref "U5") (pin "3") (pinfunction "GND_3") (pintype "power_in"))
      (node (ref "Y1") (pin "2") (pinfunction "2_2") (pintype "passive"))
      (node (ref "Y1") (pin "4") (pinfunction "4_4") (pintype "passive"))
    )
    (net (code "106") (name "Net-(C41-Pad1)") (class "Default")
      (node (ref "C41") (pin "1") (pinfunction "1_1") (pintype "passive"))
      (node (ref "R6") (pin "1") (pinfunction "1_1") (pintype "passive"))
    )
    (net (code "107") (name "Net-(D2-K)") (class "Default")
      (node (ref "D2") (pin "2") (pinfunction "K_2") (pintype "passive"))
      (node (ref "J3") (pin "1") (pinfunction "1_1") (pintype "passive"))
    )
    (net (code "108") (name "Net-(D6-K)") (class "Default")
      (node (ref "D6") (pin "2") (pinfunction "K_2") (pintype "passive"))
      (node (ref "J12") (pin "1") (pinfunction "1_1") (pintype "passive"))
    )
    (net (code "109") (name "Net-(LED1-1)") (class "Default")
      (node (ref "LED1") (pin "A") (pinfunction "1_A") (pintype "passive"))
      (node (ref "R1") (pin "1") (pinfunction "1_1") (pintype "passive"))
    )
    (net (code "110") (name "Net-(U1-DCDC_LN1)") (class "Default")
      (node (ref "C21") (pin "1") (pinfunction "1_1") (pintype "passive"))
      (node (ref "L1") (pin "1") (pinfunction "1_1") (pintype "passive"))
      (node (ref "U1") (pin "97") (pinfunction "DCDC_LN1_97") (pintype "passive"))
    )
    (net (code "111") (name "Net-(U1-DCDC_LP)") (class "Default")
      (node (ref "C30") (pin "1") (pinfunction "1_1") (pintype "passive"))
      (node (ref "L1") (pin "2") (pinfunction "2_2") (pintype "passive"))
      (node (ref "U1") (pin "99") (pinfunction "DCDC_LP_99") (pintype "passive"))
    )
    (net (code "112") (name "Net-(U1-PSWITCH)") (class "Default")
      (node (ref "R8") (pin "1") (pinfunction "1_1") (pintype "passive"))
      (node (ref "U1") (pin "119") (pinfunction "PSWITCH_119") (pintype "passive"))
    )
    (net (code "113") (name "Net-(U1-VAG)") (class "Default")
      (node (ref "C37") (pin "1") (pinfunction "1_1") (pintype "passive"))
      (node (ref "U1") (pin "117") (pinfunction "VAG_117") (pintype "passive"))
    )
    (net (code "114") (name "Net-(U1-XTALI)") (class "Default")
      (node (ref "C33") (pin "1") (pinfunction "1_1") (pintype "passive"))
      (node (ref "U1") (pin "122") (pinfunction "XTALI_122") (pintype "passive"))
      (node (ref "Y1") (pin "3") (pinfunction "3_3") (pintype "passive"))
    )
    (net (code "115") (name "Net-(U1-XTALO)") (class "Default")
      (node (ref "C35") (pin "1") (pinfunction "1_1") (pintype "passive"))
      (node (ref "U1") (pin "121") (pinfunction "XTALO_121") (pintype "passive"))
      (node (ref "Y1") (pin "1") (pinfunction "1_1") (pintype "passive"))
    )
    (net (code "116") (name "Net-(U2-VREF)") (class "Default")
      (node (ref "C34") (pin "2") (pinfunction "2_2") (pintype "passive"))
      (node (ref "C36") (pin "1") (pinfunction "1_1") (pintype "passive"))
      (node (ref "R4") (pin "1") (pinfunction "1_1") (pintype "passive"))
      (node (ref "R5") (pin "1") (pinfunction "1_1") (pintype "passive"))
      (node (ref "U2") (pin "49") (pinfunction "VREF_49") (pintype "passive"))
    )
    (net (code "117") (name "Net-(U4-OUT)") (class "Default")
      (node (ref "R13") (pin "2") (pinfunction "2_2") (pintype "passive"))
      (node (ref "U4") (pin "4") (pinfunction "OUT_4") (pintype "output"))
    )
    (net (code "118") (name "Net-(U5-OUT)") (class "Default")
      (node (ref "R14") (pin "2") (pinfunction "2_2") (pintype "passive"))
      (node (ref "U5") (pin "4") (pinfunction "OUT_4") (pintype "output"))
    )
    (net (code "119") (name "VBAT") (class "Default")
      (node (ref "C18") (pin "1") (pinfunction "1_1") (pintype "passive"))
      (node (ref "C19") (pin "1") (pinfunction "1_1") (pintype "passive"))
      (node (ref "C20") (pin "1") (pinfunction "1_1") (pintype "passive"))
      (node (ref "D1") (pin "1") (pinfunction "A_1") (pintype "passive"))
      (node (ref "J5") (pin "1") (pinfunction "1_1") (pintype "passive"))
      (node (ref "U1") (pin "100") (pinfunction "DCDC_BATTERY_100") (pintype "passive"))
      (node (ref "U1") (pin "103") (pinfunction "BATT_103") (pintype "passive"))
    )
    (net (code "120") (name "VDD4P2") (class "Default")
      (node (ref "C8") (pin "1") (pinfunction "1_1") (pintype "passive"))
      (node (ref "C9") (pin "1") (pinfunction "1_1") (pintype "passive"))
      (node (ref "D1") (pin "2") (pinfunction "K_2") (pintype "passive"))
      (node (ref "U1") (pin "101") (pinfunction "VDD4P2_101") (pintype "passive"))
    )
    (net (code "121") (name "VDDA") (class "Default")
      (node (ref "C16") (pin "1") (pinfunction "1_1") (pintype "passive"))
      (node (ref "C17") (pin "1") (pinfunction "1_1") (pintype "passive"))
      (node (ref "C38") (pin "1") (pinfunction "1_1") (pintype "passive"))
      (node (ref "U1") (pin "110") (pinfunction "VDDA1_110") (pintype "passive"))
      (node (ref "U1") (pin "96") (pinfunction "DCDC_VDDA_96") (pintype "passive"))
    )
    (net (code "122") (name "VDDD") (class "Default")
      (node (ref "C1") (pin "1") (pinfunction "1_1") (pintype "passive"))
      (node (ref "C11") (pin "1") (pinfunction "1_1") (pintype "passive"))
      (node (ref "C12") (pin "1") (pinfunction "1_1") (pintype "passive"))
      (node (ref "C2") (pin "1") (pinfunction "1_1") (pintype "passive"))
      (node (ref "U1") (pin "1") (pinfunction "VDDD1_1") (pintype "passive"))
      (node (ref "U1") (pin "93") (pinfunction "VDDD3_93") (pintype "passive"))
      (node (ref "U1") (pin "94") (pinfunction "DCDC_VDDD_94") (pintype "passive"))
    )
    (net (code "123") (name "VDDXTAL") (class "Default")
      (node (ref "C31") (pin "1") (pinfunction "1_1") (pintype "passive"))
      (node (ref "J5") (pin "3") (pinfunction "3_3") (pintype "passive"))
      (node (ref "U1") (pin "120") (pinfunction "VDDXTAL_120") (pintype "passive"))
    )
    (net (code "124") (name "unconnected-(J1-PadSW2)") (class "Default")
      (node (ref "J1") (pin "SW2") (pinfunction "SW2_SW2") (pintype "passive"))
    )
    (net (code "125") (name "unconnected-(U1-HPL-Pad113)") (class "Default")
      (node (ref "U1") (pin "113") (pinfunction "HPL_113") (pintype "passive"))
    )
    (net (code "126") (name "unconnected-(U1-HPR-Pad109)") (class "Default")
      (node (ref "U1") (pin "109") (pinfunction "HPR_109") (pintype "passive"))
    )
    (net (code "127") (name "unconnected-(U1-HP_VGND-Pad111)") (class "Default")
      (node (ref "U1") (pin "111") (pinfunction "HP_VGND_111") (pintype "passive"))
    )
    (net (code "128") (name "unconnected-(U1-LCD_D04-Pad6)") (class "Default")
      (node (ref "U1") (pin "6") (pinfunction "LCD_D04_6") (pintype "passive"))
    )
    (net (code "129") (name "unconnected-(U1-LCD_D05-Pad7)") (class "Default")
      (node (ref "U1") (pin "7") (pinfunction "LCD_D05_7") (pintype "passive"))
    )
    (net (code "130") (name "unconnected-(U1-LCD_D06-Pad8)") (class "Default")
      (node (ref "U1") (pin "8") (pinfunction "LCD_D06_8") (pintype "passive"))
    )
    (net (code "131") (name "unconnected-(U1-LCD_D07-Pad9)") (class "Default")
      (node (ref "U1") (pin "9") (pinfunction "LCD_D07_9") (pintype "passive"))
    )
    (net (code "132") (name "unconnected-(U1-LCD_DOTCK{slash}GPMI_RDY3-Pad17)") (class "Default")
      (node (ref "U1") (pin "17") (pinfunction "LCD_DOTCK/GPMI_RDY3_17") (pintype "passive"))
    )
    (net (code "133") (name "unconnected-(U1-LCD_RESET{slash}GPMI_CE3N-Pad12)") (class "Default")
      (node (ref "U1") (pin "12") (pinfunction "LCD_RESET/GPMI_CE3N_12") (pintype "passive"))
    )
    (net (code "134") (name "unconnected-(U1-LCD_VSYNC{slash}LCD_BUSY-Pad16)") (class "Default")
      (node (ref "U1") (pin "16") (pinfunction "LCD_VSYNC/LCD_BUSY_16") (pintype "passive"))
    )
    (net (code "135") (name "unconnected-(U1-LINE1_INL-Pad115)") (class "Default")
      (node (ref "U1") (pin "115") (pinfunction "LINE1_INL_115") (pintype "passive"))
    )
    (net (code "136") (name "unconnected-(U1-LINE1_INR-Pad114)") (class "Default")
      (node (ref "U1") (pin "114") (pinfunction "LINE1_INR_114") (pintype "passive"))
    )
    (net (code "137") (name "unconnected-(U1-MIC-Pad116)") (class "Default")
      (node (ref "U1") (pin "116") (pinfunction "MIC_116") (pintype "passive"))
    )
    (net (code "138") (name "unconnected-(U1-VDAC1-Pad104)") (class "Default")
      (node (ref "U1") (pin "104") (pinfunction "VDAC1_104") (pintype "passive"))
    )
    (net (code "139") (name "unconnected-(U2-NC1-Pad14)") (class "Default")
      (node (ref "U2") (pin "14") (pinfunction "NC1_14") (pintype "passive"))
    )
    (net (code "140") (name "unconnected-(U2-NC2-Pad17)") (class "Default")
      (node (ref "U2") (pin "17") (pinfunction "NC2_17") (pintype "passive"))
    )
    (net (code "141") (name "unconnected-(U2-NC3-Pad19)") (class "Default")
      (node (ref "U2") (pin "19") (pinfunction "NC3_19") (pintype "passive"))
    )
    (net (code "142") (name "unconnected-(U2-NC4-Pad25)") (class "Default")
      (node (ref "U2") (pin "25") (pinfunction "NC4_25") (pintype "passive"))
    )
    (net (code "143") (name "unconnected-(U2-NC5-Pad43)") (class "Default")
      (node (ref "U2") (pin "43") (pinfunction "NC5_43") (pintype "passive"))
    )
    (net (code "144") (name "unconnected-(U2-NC6-Pad50)") (class "Default")
      (node (ref "U2") (pin "50") (pinfunction "NC6_50") (pintype "passive"))
    )
    (net (code "145") (name "unconnected-(U2-NC7-Pad53)") (class "Default")
      (node (ref "U2") (pin "53") (pinfunction "NC7_53") (pintype "passive"))
    )
    (net (code "146") (name "unconnected-(U4-Pad1)") (class "Default")
      (node (ref "U4") (pin "1") (pinfunction "1_1") (pintype "passive"))
    )
    (net (code "147") (name "unconnected-(U5-Pad1)") (class "Default")
      (node (ref "U5") (pin "1") (pinfunction "1_1") (pintype "passive"))
    )
  )
)
